# esp-batterynode-01.net
KiCad netlist of a schematic drawn in EAGLE
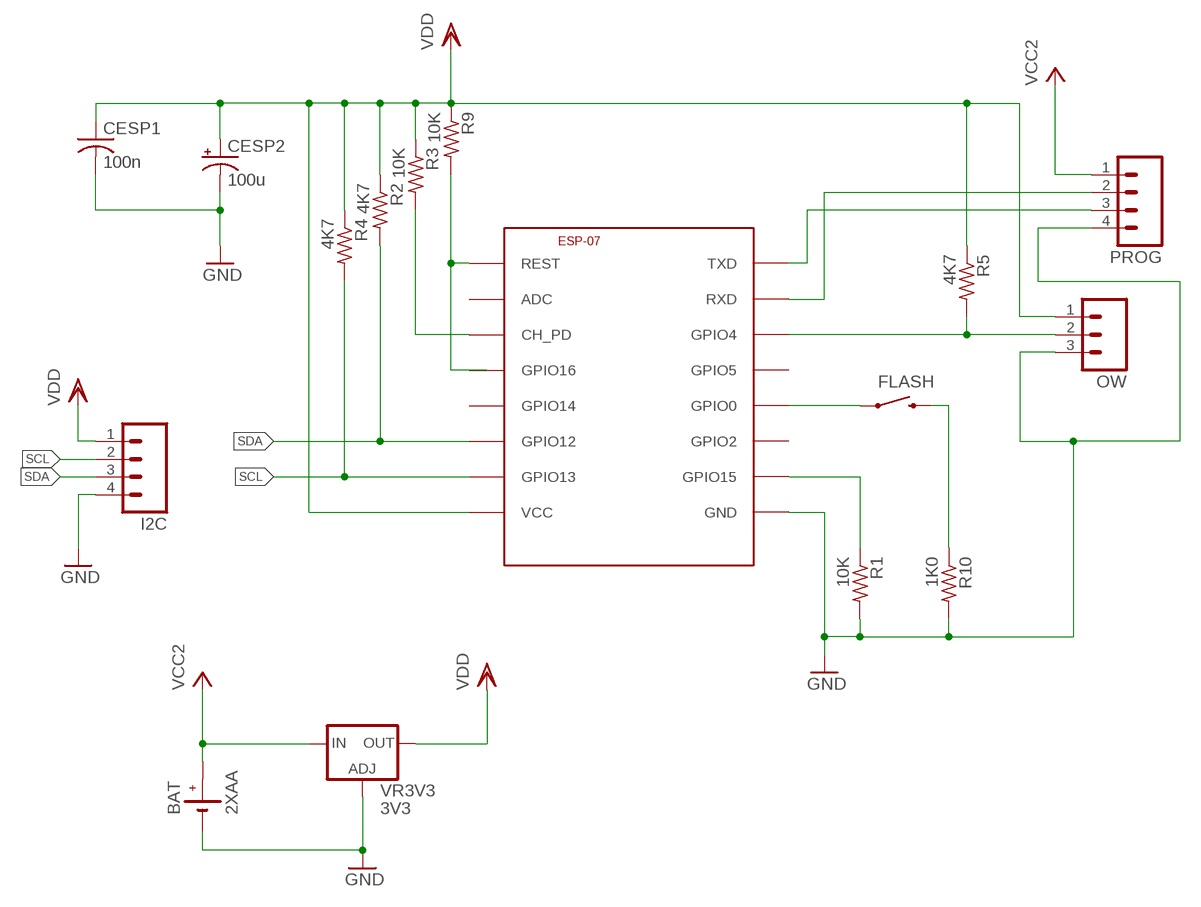
[diagram p0: schematic, sheet 1]

(export (version "E")
  (design (tool "Eeschema 10.0.6"))
  (components
    (comp (ref "BAT")
      (value "2XAA")
      (footprint "eagle-import:KEYSTONE-2XAA")
      (libsource (lib "eagle-import") (part "2XAA"))
    )
    (comp (ref "CESP1")
      (value "100n")
      (footprint "eagle-import:C0603")
      (libsource (lib "eagle-import") (part "C-USC0603"))
    )
    (comp (ref "CESP2")
      (value "100u")
      (footprint "eagle-import:E2,5-5")
      (libsource (lib "eagle-import") (part "CPOL-USE2.5-5"))
    )
    (comp (ref "ESP-07")
      (value "ESP8266-07")
      (footprint "eagle-import:ESP-07")
      (libsource (lib "eagle-import") (part "ESP8266-07"))
    )
    (comp (ref "FLASH")
      (value "SWITCH-MOMENTARY-2")
      (footprint "eagle-import:TACTILE_SWITCH_TALL")
      (libsource (lib "eagle-import") (part "SWITCH-MOMENTARY-2"))
    )
    (comp (ref "I2C")
      (value "M04LOCK_LONGPADS")
      (footprint "eagle-import:1X04_LOCK_LONGPADS")
      (libsource (lib "eagle-import") (part "M04LOCK_LONGPADS"))
    )
    (comp (ref "OW")
      (value "M03LOCK_LONGPADS")
      (footprint "eagle-import:1X03_LOCK_LONGPADS")
      (libsource (lib "eagle-import") (part "M03LOCK_LONGPADS"))
    )
    (comp (ref "PROG")
      (value "M04LOCK")
      (footprint "eagle-import:1X04_LOCK")
      (libsource (lib "eagle-import") (part "M04LOCK"))
    )
    (comp (ref "R1")
      (value "10K")
      (footprint "eagle-import:R0603")
      (libsource (lib "eagle-import") (part "R-US_R0603"))
    )
    (comp (ref "R2")
      (value "4K7")
      (footprint "eagle-import:R0603")
      (libsource (lib "eagle-import") (part "R-US_R0603"))
    )
    (comp (ref "R3")
      (value "10K")
      (footprint "eagle-import:R0603")
      (libsource (lib "eagle-import") (part "R-US_R0603"))
    )
    (comp (ref "R4")
      (value "4K7")
      (footprint "eagle-import:R0603")
      (libsource (lib "eagle-import") (part "R-US_R0603"))
    )
    (comp (ref "R5")
      (value "4K7")
      (footprint "eagle-import:R0603")
      (libsource (lib "eagle-import") (part "R-US_R0603"))
    )
    (comp (ref "R9")
      (value "10K")
      (footprint "eagle-import:R0603")
      (libsource (lib "eagle-import") (part "R-US_R0603"))
    )
    (comp (ref "R10")
      (value "1K0")
      (footprint "eagle-import:R0603")
      (libsource (lib "eagle-import") (part "R-US_R0603"))
    )
    (comp (ref "VR3V3")
      (value "3V3")
      (footprint "eagle-import:317TS")
      (libsource (lib "eagle-import") (part "LM317TS"))
    )
  )
  (nets
    (net (code "1") (name "GND") (class "Default")
      (node (ref "BAT") (pin "NEG") (pinfunction "-_NEG") (pintype "power_in"))
      (node (ref "CESP1") (pin "2") (pinfunction "2_2") (pintype "passive"))
      (node (ref "CESP2") (pin "-") (pinfunction "-_-") (pintype "passive"))
      (node (ref "ESP-07") (pin "GND") (pinfunction "GND_GND") (pintype "power_in"))
      (node (ref "I2C") (pin "4") (pinfunction "4_4") (pintype "passive"))
      (node (ref "OW") (pin "3") (pinfunction "3_3") (pintype "passive"))
      (node (ref "PROG") (pin "4") (pinfunction "4_4") (pintype "passive"))
      (node (ref "R1") (pin "2") (pinfunction "2_2") (pintype "passive"))
      (node (ref "R10") (pin "2") (pinfunction "2_2") (pintype "passive"))
      (node (ref "VR3V3") (pin "1") (pinfunction "ADJ_1") (pintype "input"))
    )
    (net (code "2") (name "Net-(ESP-07-PadCH_PD)") (class "Default")
      (node (ref "ESP-07") (pin "CH_PD") (pinfunction "CH_PD_CH_PD") (pintype "input"))
      (node (ref "R3") (pin "2") (pinfunction "2_2") (pintype "passive"))
    )
    (net (code "3") (name "Net-(ESP-07-PadGPIO4)") (class "Default")
      (node (ref "ESP-07") (pin "GPIO4") (pinfunction "GPIO4_GPIO4") (pintype "bidirectional"))
      (node (ref "OW") (pin "2") (pinfunction "2_2") (pintype "passive"))
      (node (ref "R5") (pin "2") (pinfunction "2_2") (pintype "passive"))
    )
    (net (code "4") (name "Net-(ESP-07-PadGPIO15)") (class "Default")
      (node (ref "ESP-07") (pin "GPIO15") (pinfunction "GPIO15_GPIO15") (pintype "input"))
      (node (ref "R1") (pin "1") (pinfunction "1_1") (pintype "passive"))
    )
    (net (code "5") (name "Net-(ESP-07-PadREST)") (class "Default")
      (node (ref "ESP-07") (pin "REST") (pinfunction "REST_REST") (pintype "bidirectional"))
      (node (ref "R9") (pin "2") (pinfunction "2_2") (pintype "passive"))
    )
    (net (code "6") (name "Net-(ESP-07-PadRXD)") (class "Default")
      (node (ref "ESP-07") (pin "RXD") (pinfunction "RXD_RXD") (pintype "input"))
      (node (ref "PROG") (pin "2") (pinfunction "2_2") (pintype "passive"))
    )
    (net (code "7") (name "Net-(ESP-07-PadTXD)") (class "Default")
      (node (ref "ESP-07") (pin "TXD") (pinfunction "TXD_TXD") (pintype "output"))
      (node (ref "PROG") (pin "3") (pinfunction "3_3") (pintype "passive"))
    )
    (net (code "8") (name "Net-(FLASH-1)") (class "Default")
      (node (ref "ESP-07") (pin "GPIO0") (pinfunction "GPIO0_GPIO0") (pintype "bidirectional"))
      (node (ref "FLASH") (pin "A2") (pinfunction "1_A2") (pintype "passive"))
    )
    (net (code "9") (name "Net-(FLASH-2)") (class "Default")
      (node (ref "FLASH") (pin "B2") (pinfunction "2_B2") (pintype "passive"))
      (node (ref "R10") (pin "1") (pinfunction "1_1") (pintype "passive"))
    )
    (net (code "10") (name "SCL") (class "Default")
      (node (ref "ESP-07") (pin "GPIO13") (pinfunction "GPIO13_GPIO13") (pintype "bidirectional"))
      (node (ref "I2C") (pin "2") (pinfunction "2_2") (pintype "passive"))
      (node (ref "R4") (pin "2") (pinfunction "2_2") (pintype "passive"))
    )
    (net (code "11") (name "SDA") (class "Default")
      (node (ref "ESP-07") (pin "GPIO12") (pinfunction "GPIO12_GPIO12") (pintype "bidirectional"))
      (node (ref "I2C") (pin "3") (pinfunction "3_3") (pintype "passive"))
      (node (ref "R2") (pin "2") (pinfunction "2_2") (pintype "passive"))
    )
    (net (code "12") (name "VCC2") (class "Default")
      (node (ref "BAT") (pin "POS") (pinfunction "+_POS") (pintype "power_in"))
      (node (ref "PROG") (pin "1") (pinfunction "1_1") (pintype "passive"))
      (node (ref "VR3V3") (pin "3") (pinfunction "IN_3") (pintype "input"))
    )
    (net (code "13") (name "VDD") (class "Default")
      (node (ref "CESP1") (pin "1") (pinfunction "1_1") (pintype "passive"))
      (node (ref "CESP2") (pin "+") (pinfunction "+_+") (pintype "passive"))
      (node (ref "ESP-07") (pin "VCC") (pinfunction "VCC_VCC") (pintype "power_in"))
      (node (ref "I2C") (pin "1") (pinfunction "1_1") (pintype "passive"))
      (node (ref "OW") (pin "1") (pinfunction "1_1") (pintype "passive"))
      (node (ref "R2") (pin "1") (pinfunction "1_1") (pintype "passive"))
      (node (ref "R3") (pin "1") (pinfunction "1_1") (pintype "passive"))
      (node (ref "R4") (pin "1") (pinfunction "1_1") (pintype "passive"))
      (node (ref "R5") (pin "1") (pinfunction "1_1") (pintype "passive"))
      (node (ref "R9") (pin "1") (pinfunction "1_1") (pintype "passive"))
      (node (ref "VR3V3") (pin "2") (pinfunction "OUT_2") (pintype "passive"))
    )
    (net (code "14") (name "unconnected-(ESP-07-PadADC)") (class "Default")
      (node (ref "ESP-07") (pin "ADC") (pinfunction "ADC_ADC") (pintype "bidirectional"))
    )
    (net (code "15") (name "unconnected-(ESP-07-PadGPIO2)") (class "Default")
      (node (ref "ESP-07") (pin "GPIO2") (pinfunction "GPIO2_GPIO2") (pintype "bidirectional"))
    )
    (net (code "16") (name "unconnected-(ESP-07-PadGPIO5)") (class "Default")
      (node (ref "ESP-07") (pin "GPIO5") (pinfunction "GPIO5_GPIO5") (pintype "bidirectional"))
    )
    (net (code "17") (name "unconnected-(ESP-07-PadGPIO14)") (class "Default")
      (node (ref "ESP-07") (pin "GPIO14") (pinfunction "GPIO14_GPIO14") (pintype "bidirectional"))
    )
    (net (code "18") (name "unconnected-(ESP-07-PadGPIO16)") (class "Default")
      (node (ref "ESP-07") (pin "GPIO16") (pinfunction "GPIO16_GPIO16") (pintype "bidirectional"))
    )
  )
)
